# Spanungsversorgung.net
KiCad netlist of a schematic drawn in Altium Designer
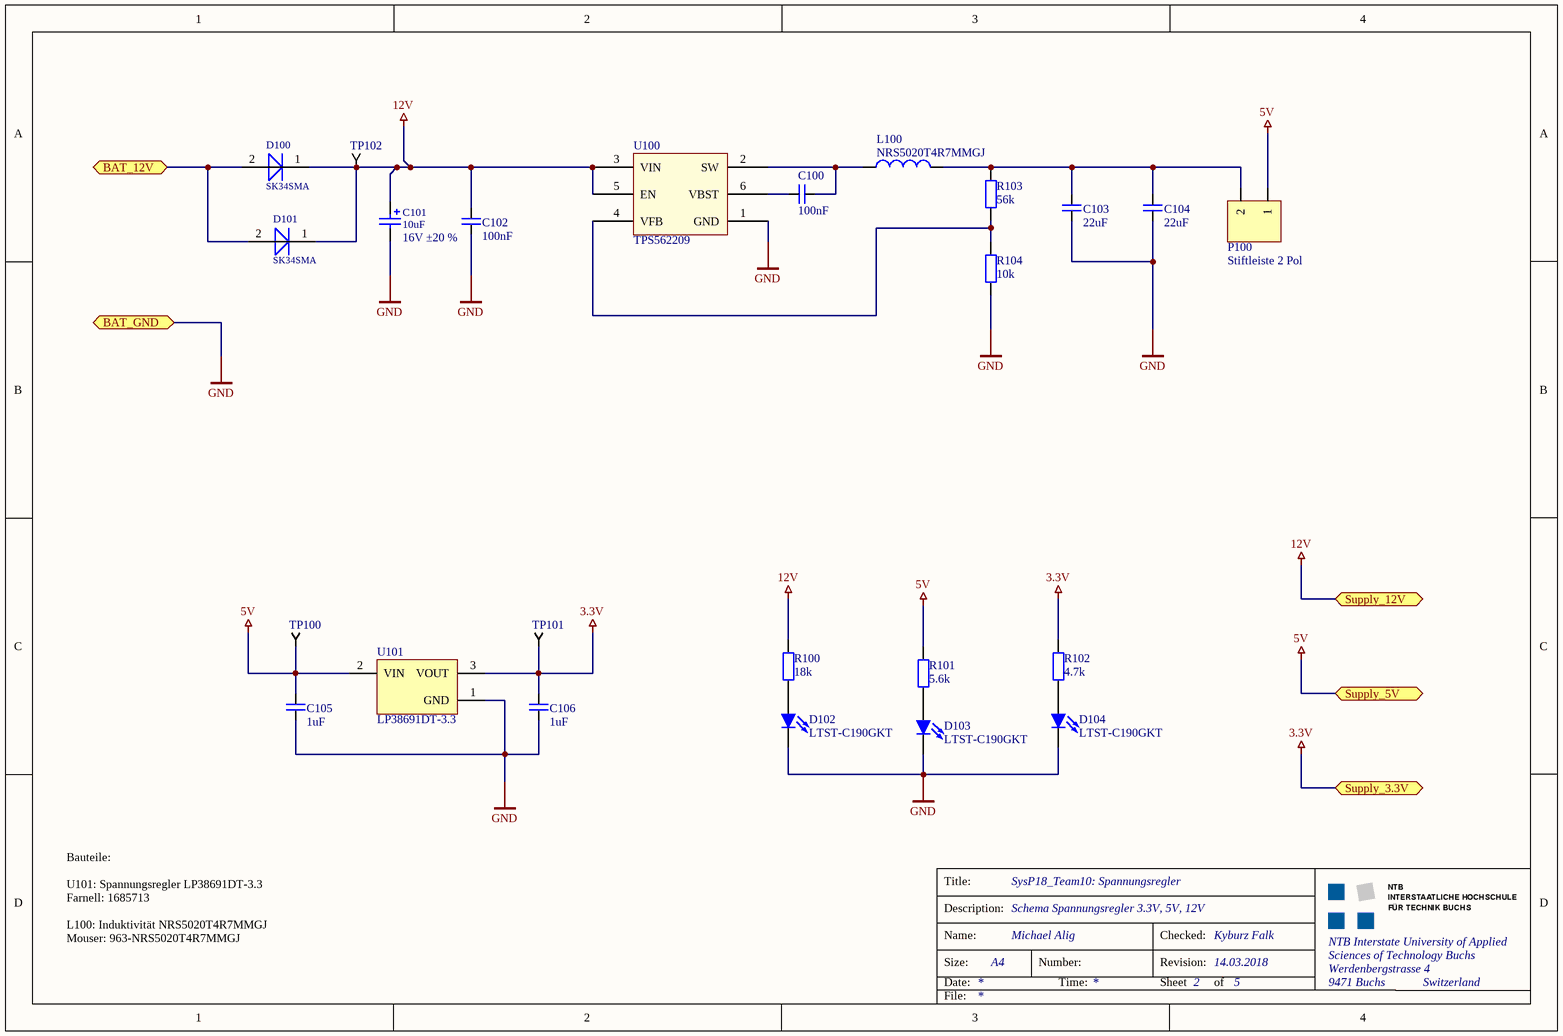
[diagram p0: Spanungsversorgung.SchDoc]

(export (version "E")
  (design (tool "Eeschema 10.0.6"))
  (components
    (comp (ref "C100")
      (value "100nF")
      (footprint "CAPC0805")
      (description "X7R MLCC 0805 (2012 Metric)")
      (fields (field (name "TOLERANCE") "10%"))
      (libsource (lib "Motorentreiber") (part "C Bipolar 0805"))
    )
    (comp (ref "C101")
      (value "10uF")
      (footprint "CDE_CAP AVE CODE D_H")
      (description "Aluminum Electrolytic Capacitors for Filtering and Bypass, 47uF, 16V")
      (fields
        (field (name "MANUFACTURER") "Cornell Dubilier")
        (field (name "VALUEADDON") "16V ±20 %")
        (field (name "Comment") "AVE476M16D16T-F")
        (field (name "PUBLISHER") "Stefan Ursella, M.Eng")
      )
      (libsource (lib "Motorentreiber") (part "CDE_AVE476M16D16T-F_AVE CODE D"))
    )
    (comp (ref "C102")
      (value "100nF")
      (footprint "CAPC0805")
      (description "X7R MLCC 0805 (2012 Metric)")
      (fields (field (name "TOLERANCE") "10%"))
      (libsource (lib "Motorentreiber") (part "C Bipolar 0805"))
    )
    (comp (ref "C103")
      (value "22uF")
      (footprint "CAPC1206")
      (description "X7R MLCC 1206 (3016 Metric)")
      (fields (field (name "TOLERANCE") "10%"))
      (libsource (lib "Motorentreiber") (part "C Bipolar 1206"))
    )
    (comp (ref "C104")
      (value "22uF")
      (footprint "CAPC1206")
      (description "X7R MLCC 1206 (3016 Metric)")
      (fields (field (name "TOLERANCE") "10%"))
      (libsource (lib "Motorentreiber") (part "C Bipolar 1206"))
    )
    (comp (ref "C105")
      (value "1uF")
      (footprint "CAPC0805")
      (description "X7R MLCC 0805 (2012 Metric)")
      (fields (field (name "TOLERANCE") "10%"))
      (libsource (lib "Motorentreiber") (part "C Bipolar 0805"))
    )
    (comp (ref "C106")
      (value "1uF")
      (footprint "CAPC0805")
      (description "X7R MLCC 0805 (2012 Metric)")
      (fields (field (name "TOLERANCE") "10%"))
      (libsource (lib "Motorentreiber") (part "C Bipolar 0805"))
    )
    (comp (ref "D100")
      (value "SK34SMA")
      (footprint "DIOTEC_DO-214AC_1K2A_2_H")
      (fields
        (field (name "MANUFACTURER") "Diotec Semiconductor")
        (field (name "PUBLISHER") "Stefan Ursella, M.Eng")
      )
      (libsource (lib "Motorentreiber") (part "DIOTEC_SK34SMA_DO-214AC"))
    )
    (comp (ref "D101")
      (value "SK34SMA")
      (footprint "DIOTEC_DO-214AC_1K2A_2_H")
      (fields
        (field (name "MANUFACTURER") "Diotec Semiconductor")
        (field (name "PUBLISHER") "Stefan Ursella, M.Eng")
      )
      (libsource (lib "Motorentreiber") (part "DIOTEC_SK34SMA_DO-214AC"))
    )
    (comp (ref "D102")
      (value "LTST-C190GKT")
      (footprint "LED 0603 green")
      (description "LED SMD 0603 green 6mcd")
      (libsource (lib "Motorentreiber") (part "LED"))
    )
    (comp (ref "D103")
      (value "LTST-C190GKT")
      (footprint "LED 0603 green")
      (description "LED SMD 0603 green 6mcd")
      (libsource (lib "Motorentreiber") (part "LED"))
    )
    (comp (ref "D104")
      (value "LTST-C190GKT")
      (footprint "LED 0603 green")
      (description "LED SMD 0603 green 6mcd")
      (libsource (lib "Motorentreiber") (part "LED"))
    )
    (comp (ref "L100")
      (value "NRS5020T4R7MMGJ")
      (footprint "NRS5024T4R7MMGJV")
      (description "Tayo Yuden NRS5020T4R7MMGJ 4u7 2A")
      (libsource (lib "Schemasymbole") (part "NRS5020T4R7MMGJ"))
    )
    (comp (ref "P100")
      (value "Stiftleiste 2 Pol")
      (footprint "2Pin Header 2.54mm")
      (libsource (lib "altium-import") (part "root_3_2 Pin Connector_"))
    )
    (comp (ref "R100")
      (value "18k")
      (footprint "GEN_R0805_H")
      (description "generic resistor")
      (fields
        (field (name "MANUFACTURER") "Tbd")
        (field (name "Comment") "Generic")
        (field (name "PUBLISHER") "Altium Limited")
      )
      (libsource (lib "Motorentreiber") (part "GEN_R_2"))
    )
    (comp (ref "R101")
      (value "5.6k")
      (footprint "GEN_R0805_H")
      (description "generic resistor")
      (fields
        (field (name "MANUFACTURER") "Tbd")
        (field (name "Comment") "Generic")
        (field (name "PUBLISHER") "Altium Limited")
      )
      (libsource (lib "Motorentreiber") (part "GEN_R_2"))
    )
    (comp (ref "R102")
      (value "4.7k")
      (footprint "GEN_R0805_H")
      (description "generic resistor")
      (fields
        (field (name "MANUFACTURER") "Tbd")
        (field (name "Comment") "Generic")
        (field (name "PUBLISHER") "Altium Limited")
      )
      (libsource (lib "Motorentreiber") (part "GEN_R_2"))
    )
    (comp (ref "R103")
      (value "56k")
      (footprint "GEN_R0805_H")
      (description "generic resistor")
      (fields
        (field (name "MANUFACTURER") "Tbd")
        (field (name "Comment") "Generic")
        (field (name "PUBLISHER") "Altium Limited")
      )
      (libsource (lib "Motorentreiber") (part "GEN_R_2"))
    )
    (comp (ref "R104")
      (value "10k")
      (footprint "GEN_R0805_H")
      (description "generic resistor")
      (fields
        (field (name "MANUFACTURER") "Tbd")
        (field (name "Comment") "Generic")
        (field (name "PUBLISHER") "Altium Limited")
      )
      (libsource (lib "Motorentreiber") (part "GEN_R_2"))
    )
    (comp (ref "TP100")
      (value "Testpoint xSmall")
      (footprint "TP_SMD_xsmall")
      (libsource (lib "Motorentreiber") (part "Testpoint small"))
    )
    (comp (ref "TP101")
      (value "Testpoint xSmall")
      (footprint "TP_SMD_xsmall")
      (libsource (lib "Motorentreiber") (part "Testpoint small"))
    )
    (comp (ref "TP102")
      (value "Testpoint xSmall")
      (footprint "TP_SMD_xsmall")
      (libsource (lib "Motorentreiber") (part "Testpoint small"))
    )
    (comp (ref "U100")
      (value "TPS562209")
      (footprint "SOT23-6")
      (description "3-A Synchronous Step-Down Voltage Regulator")
      (libsource (lib "Motorentreiber") (part "TPS562209"))
    )
    (comp (ref "U101")
      (value "LP38691DT-3.3")
      (footprint "TO-92-TO3")
      (description "Low Quiescent Current LDO, 3-Pin TO-92, Extended TemperatureBAG")
      (fields (field (name "PUBLISHER") "Altium Limited"))
      (libsource (lib "Microchip Power Mgt Line Regulator") (part "MCP1700-1202E/TO"))
    )
  )
  (nets
    (net (code "1") (name "/BAT_12V") (class "Default")
      (node (ref "D100") (pin "2") (pinfunction "A_2") (pintype "passive"))
      (node (ref "D101") (pin "2") (pinfunction "A_2") (pintype "passive"))
    )
    (net (code "2") (name "3.3V") (class "Default")
      (node (ref "C106") (pin "1") (pinfunction "1_1") (pintype "passive"))
      (node (ref "R102") (pin "2") (pinfunction "2_2") (pintype "passive"))
      (node (ref "TP101") (pin "1") (pinfunction "0_1") (pintype "passive"))
      (node (ref "U101") (pin "3") (pinfunction "VOUT_3") (pintype "power_in"))
    )
    (net (code "3") (name "5V") (class "Default")
      (node (ref "C105") (pin "1") (pinfunction "1_1") (pintype "passive"))
      (node (ref "P100") (pin "1") (pinfunction "1_1") (pintype "passive"))
      (node (ref "R101") (pin "2") (pinfunction "2_2") (pintype "passive"))
      (node (ref "TP100") (pin "1") (pinfunction "0_1") (pintype "passive"))
      (node (ref "U101") (pin "2") (pinfunction "VIN_2") (pintype "power_in"))
    )
    (net (code "4") (name "12V") (class "Default")
      (node (ref "C101") (pin "1") (pinfunction "Pos_1") (pintype "passive"))
      (node (ref "C102") (pin "1") (pinfunction "1_1") (pintype "passive"))
      (node (ref "D100") (pin "1") (pinfunction "K_1") (pintype "passive"))
      (node (ref "D101") (pin "1") (pinfunction "K_1") (pintype "passive"))
      (node (ref "R100") (pin "2") (pinfunction "2_2") (pintype "passive"))
      (node (ref "TP102") (pin "1") (pinfunction "0_1") (pintype "passive"))
      (node (ref "U100") (pin "3") (pinfunction "VIN_3") (pintype "passive"))
      (node (ref "U100") (pin "5") (pinfunction "EN_5") (pintype "passive"))
    )
    (net (code "5") (name "GND") (class "Default")
      (node (ref "C101") (pin "2") (pinfunction "Neg_2") (pintype "passive"))
      (node (ref "C102") (pin "2") (pinfunction "2_2") (pintype "passive"))
      (node (ref "C103") (pin "1") (pinfunction "1_1") (pintype "passive"))
      (node (ref "C104") (pin "2") (pinfunction "2_2") (pintype "passive"))
      (node (ref "C105") (pin "2") (pinfunction "2_2") (pintype "passive"))
      (node (ref "C106") (pin "2") (pinfunction "2_2") (pintype "passive"))
      (node (ref "D102") (pin "1") (pinfunction "K_1") (pintype "passive"))
      (node (ref "D103") (pin "1") (pinfunction "K_1") (pintype "passive"))
      (node (ref "D104") (pin "1") (pinfunction "K_1") (pintype "passive"))
      (node (ref "R104") (pin "1") (pinfunction "1_1") (pintype "passive"))
      (node (ref "U100") (pin "1") (pinfunction "GND_1") (pintype "passive"))
      (node (ref "U101") (pin "1") (pinfunction "GND_1") (pintype "power_in"))
    )
    (net (code "6") (name "Net-(C103-Pad2)") (class "Default")
      (node (ref "C103") (pin "2") (pinfunction "2_2") (pintype "passive"))
      (node (ref "C104") (pin "1") (pinfunction "1_1") (pintype "passive"))
      (node (ref "L100") (pin "2") (pinfunction "2_2") (pintype "passive"))
      (node (ref "P100") (pin "2") (pinfunction "2_2") (pintype "passive"))
      (node (ref "R103") (pin "2") (pinfunction "2_2") (pintype "passive"))
    )
    (net (code "7") (name "Net-(D102-A)") (class "Default")
      (node (ref "D102") (pin "2") (pinfunction "A_2") (pintype "passive"))
      (node (ref "R100") (pin "1") (pinfunction "1_1") (pintype "passive"))
    )
    (net (code "8") (name "Net-(D103-A)") (class "Default")
      (node (ref "D103") (pin "2") (pinfunction "A_2") (pintype "passive"))
      (node (ref "R101") (pin "1") (pinfunction "1_1") (pintype "passive"))
    )
    (net (code "9") (name "Net-(D104-A)") (class "Default")
      (node (ref "D104") (pin "2") (pinfunction "A_2") (pintype "passive"))
      (node (ref "R102") (pin "1") (pinfunction "1_1") (pintype "passive"))
    )
    (net (code "10") (name "Net-(U100-SW)") (class "Default")
      (node (ref "C100") (pin "2") (pinfunction "2_2") (pintype "passive"))
      (node (ref "L100") (pin "1") (pinfunction "1_1") (pintype "passive"))
      (node (ref "U100") (pin "2") (pinfunction "SW_2") (pintype "passive"))
    )
    (net (code "11") (name "Net-(U100-VBST)") (class "Default")
      (node (ref "C100") (pin "1") (pinfunction "1_1") (pintype "passive"))
      (node (ref "U100") (pin "6") (pinfunction "VBST_6") (pintype "passive"))
    )
    (net (code "12") (name "Net-(U100-VFB)") (class "Default")
      (node (ref "R103") (pin "1") (pinfunction "1_1") (pintype "passive"))
      (node (ref "R104") (pin "2") (pinfunction "2_2") (pintype "passive"))
      (node (ref "U100") (pin "4") (pinfunction "VFB_4") (pintype "passive"))
    )
  )
)
